# xpark.net
KiCad netlist of a schematic drawn in EAGLE
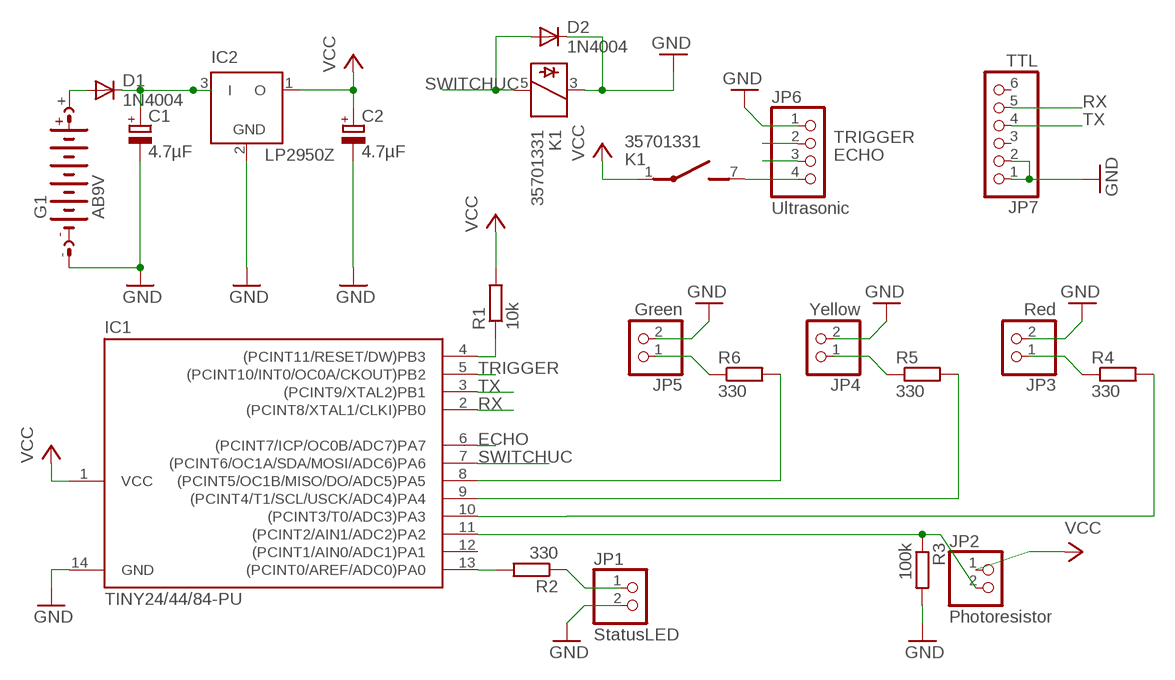
[diagram p0: schematic, sheet 1]

(export (version "E")
  (design (tool "Eeschema 10.0.6"))
  (components
    (comp (ref "C1")
      (value "4.7µF")
      (footprint "eagle-import:E2,5-5")
      (libsource (lib "eagle-import") (part "CPOL-EUE2.5-5"))
    )
    (comp (ref "C2")
      (value "4.7µF")
      (footprint "eagle-import:E2,5-5")
      (libsource (lib "eagle-import") (part "CPOL-EUE2.5-5"))
    )
    (comp (ref "D1")
      (value "1N4004")
      (footprint "eagle-import:DO41-10")
      (libsource (lib "eagle-import") (part "1N4004"))
    )
    (comp (ref "D2")
      (value "1N4004")
      (footprint "eagle-import:DO41-10")
      (libsource (lib "eagle-import") (part "1N4004"))
    )
    (comp (ref "G1")
      (value "AB9V")
      (footprint "eagle-import:AB9V")
      (libsource (lib "eagle-import") (part "AB9V"))
    )
    (comp (ref "IC1")
      (value "TINY24/44/84-PU")
      (footprint "eagle-import:DIL14")
      (libsource (lib "eagle-import") (part "TINY24/44/84-PU"))
    )
    (comp (ref "IC2")
      (value "LP2950Z")
      (footprint "eagle-import:TO92")
      (libsource (lib "eagle-import") (part "LP2950Z"))
    )
    (comp (ref "JP1")
      (value "StatusLED")
      (footprint "eagle-import:1X02")
      (libsource (lib "eagle-import") (part "PINHD-1X2"))
    )
    (comp (ref "JP2")
      (value "Photoresistor")
      (footprint "eagle-import:1X02")
      (libsource (lib "eagle-import") (part "PINHD-1X2"))
    )
    (comp (ref "JP3")
      (value "Red")
      (footprint "eagle-import:1X02")
      (libsource (lib "eagle-import") (part "PINHD-1X2"))
    )
    (comp (ref "JP4")
      (value "Yellow")
      (footprint "eagle-import:1X02")
      (libsource (lib "eagle-import") (part "PINHD-1X2"))
    )
    (comp (ref "JP5")
      (value "Green")
      (footprint "eagle-import:1X02")
      (libsource (lib "eagle-import") (part "PINHD-1X2"))
    )
    (comp (ref "JP6")
      (value "Ultrasonic")
      (footprint "eagle-import:1X04")
      (libsource (lib "eagle-import") (part "PINHD-1X4"))
    )
    (comp (ref "JP7")
      (value "TTL")
      (footprint "eagle-import:1X06")
      (libsource (lib "eagle-import") (part "PINHD-1X6"))
    )
    (comp (ref "K1")
      (value "35701331")
      (footprint "eagle-import:REED")
      (libsource (lib "eagle-import") (part "35701331"))
    )
    (comp (ref "R1")
      (value "10k")
      (footprint "eagle-import:0204_7")
      (libsource (lib "eagle-import") (part "R-EU_0204/7"))
    )
    (comp (ref "R2")
      (value "330")
      (footprint "eagle-import:0204_7")
      (libsource (lib "eagle-import") (part "R-EU_0204/7"))
    )
    (comp (ref "R3")
      (value "100k")
      (footprint "eagle-import:0204_7")
      (libsource (lib "eagle-import") (part "R-EU_0204/7"))
    )
    (comp (ref "R4")
      (value "330")
      (footprint "eagle-import:0204_7")
      (libsource (lib "eagle-import") (part "R-EU_0204/7"))
    )
    (comp (ref "R5")
      (value "330")
      (footprint "eagle-import:0204_7")
      (libsource (lib "eagle-import") (part "R-EU_0204/7"))
    )
    (comp (ref "R6")
      (value "330")
      (footprint "eagle-import:0204_7")
      (libsource (lib "eagle-import") (part "R-EU_0204/7"))
    )
  )
  (nets
    (net (code "1") (name "/ECHO") (class "Default")
      (node (ref "IC1") (pin "6") (pinfunction "(PCINT7/ICP/OC0B/ADC7)PA7_6") (pintype "bidirectional"))
      (node (ref "JP6") (pin "3") (pinfunction "3_3") (pintype "passive"))
    )
    (net (code "2") (name "/RX") (class "Default")
      (node (ref "IC1") (pin "2") (pinfunction "(PCINT8/XTAL1/CLKI)PB0_2") (pintype "bidirectional"))
      (node (ref "JP7") (pin "5") (pinfunction "5_5") (pintype "passive"))
    )
    (net (code "3") (name "/SWITCHUC") (class "Default")
      (node (ref "D2") (pin "A") (pinfunction "A_A") (pintype "passive"))
      (node (ref "IC1") (pin "7") (pinfunction "(PCINT6/OC1A/SDA/MOSI/ADC6)PA6_7") (pintype "bidirectional"))
      (node (ref "K1") (pin "5") (pinfunction "5_5") (pintype "passive"))
    )
    (net (code "4") (name "/TRIGGER") (class "Default")
      (node (ref "IC1") (pin "5") (pinfunction "(PCINT10/INT0/OC0A/CKOUT)PB2_5") (pintype "bidirectional"))
      (node (ref "JP6") (pin "2") (pinfunction "2_2") (pintype "passive"))
    )
    (net (code "5") (name "/TX") (class "Default")
      (node (ref "IC1") (pin "3") (pinfunction "(PCINT9/XTAL2)PB1_3") (pintype "bidirectional"))
      (node (ref "JP7") (pin "4") (pinfunction "4_4") (pintype "passive"))
    )
    (net (code "6") (name "GND") (class "Default")
      (node (ref "C1") (pin "-") (pinfunction "-_-") (pintype "passive"))
      (node (ref "C2") (pin "-") (pinfunction "-_-") (pintype "passive"))
      (node (ref "D2") (pin "C") (pinfunction "C_C") (pintype "passive"))
      (node (ref "G1") (pin "-") (pinfunction "-_-") (pintype "passive"))
      (node (ref "IC1") (pin "14") (pinfunction "GND_14") (pintype "power_in"))
      (node (ref "IC2") (pin "2") (pinfunction "GND_2") (pintype "power_in"))
      (node (ref "JP1") (pin "2") (pinfunction "2_2") (pintype "passive"))
      (node (ref "JP3") (pin "2") (pinfunction "2_2") (pintype "passive"))
      (node (ref "JP4") (pin "2") (pinfunction "2_2") (pintype "passive"))
      (node (ref "JP5") (pin "2") (pinfunction "2_2") (pintype "passive"))
      (node (ref "JP6") (pin "1") (pinfunction "1_1") (pintype "passive"))
      (node (ref "JP7") (pin "1") (pinfunction "1_1") (pintype "passive"))
      (node (ref "JP7") (pin "2") (pinfunction "2_2") (pintype "passive"))
      (node (ref "K1") (pin "3") (pinfunction "3_3") (pintype "passive"))
      (node (ref "R3") (pin "2") (pinfunction "2_2") (pintype "passive"))
    )
    (net (code "7") (name "Net-(D1-PadA)") (class "Default")
      (node (ref "D1") (pin "A") (pinfunction "A_A") (pintype "passive"))
      (node (ref "G1") (pin "+") (pinfunction "+_+") (pintype "passive"))
    )
    (net (code "8") (name "Net-(IC1-(PCINT0{slash}AREF{slash}ADC0)PA0)") (class "Default")
      (node (ref "IC1") (pin "13") (pinfunction "(PCINT0/AREF/ADC0)PA0_13") (pintype "bidirectional"))
      (node (ref "R2") (pin "2") (pinfunction "2_2") (pintype "passive"))
    )
    (net (code "9") (name "Net-(IC1-(PCINT2{slash}AIN1{slash}ADC2)PA2)") (class "Default")
      (node (ref "IC1") (pin "11") (pinfunction "(PCINT2/AIN1/ADC2)PA2_11") (pintype "bidirectional"))
      (node (ref "JP2") (pin "2") (pinfunction "2_2") (pintype "passive"))
      (node (ref "R3") (pin "1") (pinfunction "1_1") (pintype "passive"))
    )
    (net (code "10") (name "Net-(IC1-(PCINT3{slash}T0{slash}ADC3)PA3)") (class "Default")
      (node (ref "IC1") (pin "10") (pinfunction "(PCINT3/T0/ADC3)PA3_10") (pintype "bidirectional"))
      (node (ref "R4") (pin "2") (pinfunction "2_2") (pintype "passive"))
    )
    (net (code "11") (name "Net-(IC1-(PCINT4{slash}T1{slash}SCL{slash}USCK{slash}ADC4)PA4)") (class "Default")
      (node (ref "IC1") (pin "9") (pinfunction "(PCINT4/T1/SCL/USCK/ADC4)PA4_9") (pintype "bidirectional"))
      (node (ref "R5") (pin "2") (pinfunction "2_2") (pintype "passive"))
    )
    (net (code "12") (name "Net-(IC1-(PCINT5{slash}OC1B{slash}MISO{slash}DO{slash}ADC5)PA5)") (class "Default")
      (node (ref "IC1") (pin "8") (pinfunction "(PCINT5/OC1B/MISO/DO/ADC5)PA5_8") (pintype "bidirectional"))
      (node (ref "R6") (pin "2") (pinfunction "2_2") (pintype "passive"))
    )
    (net (code "13") (name "Net-(IC1-(PCINT11{slash}RESET{slash}DW)PB3)") (class "Default")
      (node (ref "IC1") (pin "4") (pinfunction "(PCINT11/RESET/DW)PB3_4") (pintype "bidirectional"))
      (node (ref "R1") (pin "1") (pinfunction "1_1") (pintype "passive"))
    )
    (net (code "14") (name "Net-(IC2-I)") (class "Default")
      (node (ref "C1") (pin "+") (pinfunction "+_+") (pintype "passive"))
      (node (ref "D1") (pin "C") (pinfunction "C_C") (pintype "passive"))
      (node (ref "IC2") (pin "3") (pinfunction "I_3") (pintype "input"))
    )
    (net (code "15") (name "Net-(JP1-Pad1)") (class "Default")
      (node (ref "JP1") (pin "1") (pinfunction "1_1") (pintype "passive"))
      (node (ref "R2") (pin "1") (pinfunction "1_1") (pintype "passive"))
    )
    (net (code "16") (name "Net-(JP3-Pad1)") (class "Default")
      (node (ref "JP3") (pin "1") (pinfunction "1_1") (pintype "passive"))
      (node (ref "R4") (pin "1") (pinfunction "1_1") (pintype "passive"))
    )
    (net (code "17") (name "Net-(JP4-Pad1)") (class "Default")
      (node (ref "JP4") (pin "1") (pinfunction "1_1") (pintype "passive"))
      (node (ref "R5") (pin "1") (pinfunction "1_1") (pintype "passive"))
    )
    (net (code "18") (name "Net-(JP5-Pad1)") (class "Default")
      (node (ref "JP5") (pin "1") (pinfunction "1_1") (pintype "passive"))
      (node (ref "R6") (pin "1") (pinfunction "1_1") (pintype "passive"))
    )
    (net (code "19") (name "Net-(K1B-S)") (class "Default")
      (node (ref "JP6") (pin "4") (pinfunction "4_4") (pintype "passive"))
      (node (ref "K1") (pin "7") (pinfunction "S_7") (pintype "passive"))
    )
    (net (code "20") (name "VCC") (class "Default")
      (node (ref "C2") (pin "+") (pinfunction "+_+") (pintype "passive"))
      (node (ref "IC1") (pin "1") (pinfunction "VCC_1") (pintype "power_in"))
      (node (ref "IC2") (pin "1") (pinfunction "O_1") (pintype "input"))
      (node (ref "JP2") (pin "1") (pinfunction "1_1") (pintype "passive"))
      (node (ref "K1") (pin "1") (pinfunction "P_1") (pintype "passive"))
      (node (ref "R1") (pin "2") (pinfunction "2_2") (pintype "passive"))
    )
    (net (code "21") (name "unconnected-(IC1-(PCINT1{slash}AIN0{slash}ADC1)PA1-Pad12)") (class "Default")
      (node (ref "IC1") (pin "12") (pinfunction "(PCINT1/AIN0/ADC1)PA1_12") (pintype "bidirectional"))
    )
    (net (code "22") (name "unconnected-(JP7-Pad3)") (class "Default")
      (node (ref "JP7") (pin "3") (pinfunction "3_3") (pintype "passive"))
    )
    (net (code "23") (name "unconnected-(JP7-Pad6)") (class "Default")
      (node (ref "JP7") (pin "6") (pinfunction "6_6") (pintype "passive"))
    )
  )
)
